# LAN.net
KiCad netlist of a schematic drawn in Altium Designer
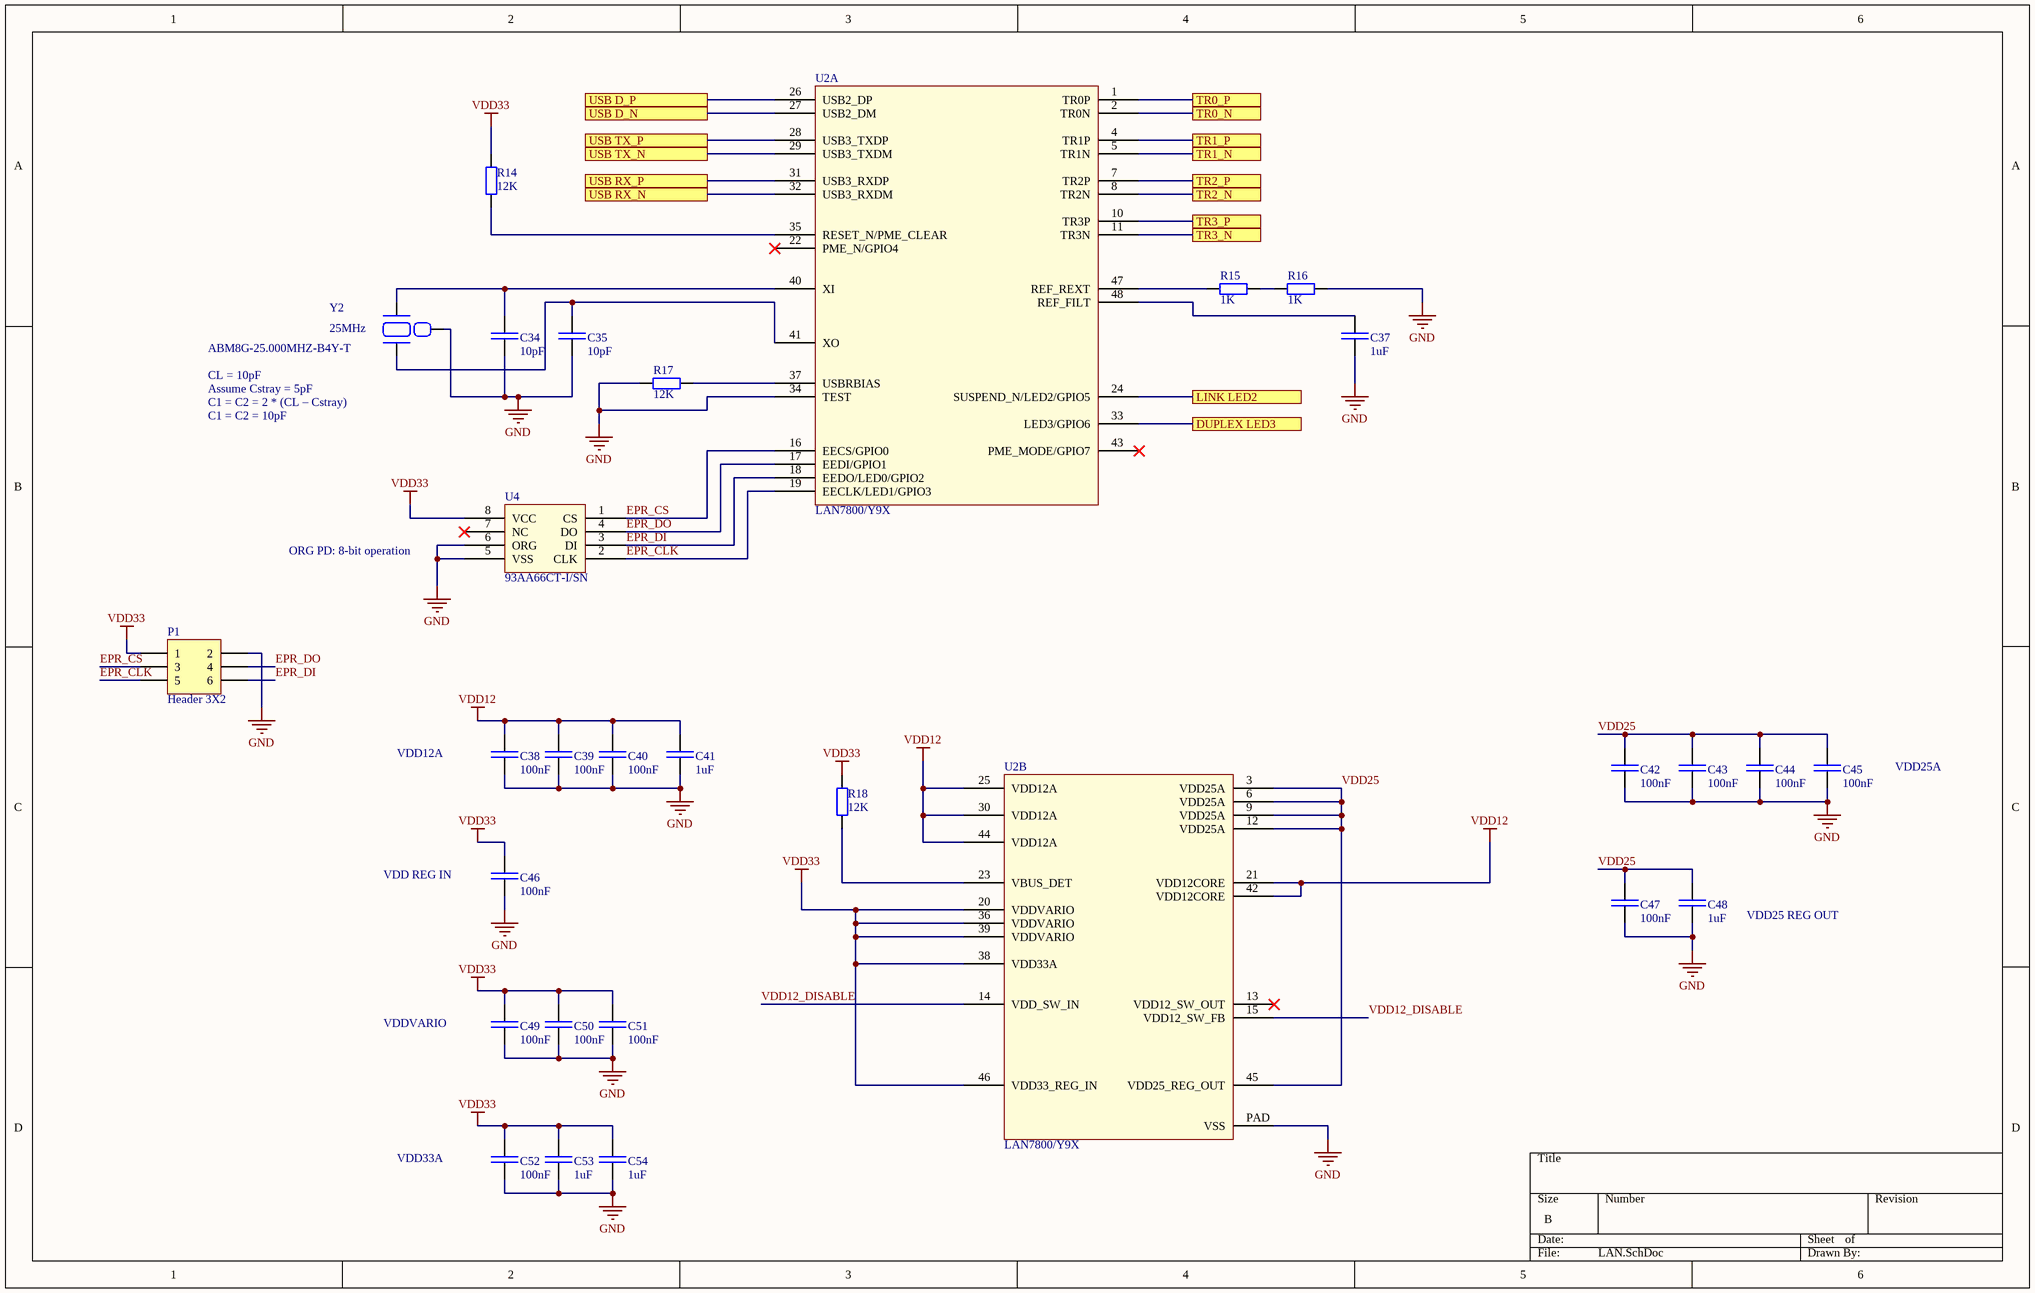
[diagram p0: LAN.SchDoc]

(export (version "E")
  (design (tool "Eeschema 10.0.6"))
  (components
    (comp (ref "C34")
      (value "10pF")
      (footprint "CAP_SM0603_YAGEOCC2_N")
      (description "CAP 10pF SM0603 NPO 50V YAGEO CC2")
      (fields
        (field (name "MANUFACTURER") "Yageo")
        (field (name "MANUFACTURER PART NUMBER") "CC0603JRNPO9BN100")
      )
      (libsource (lib "Yageo") (part "CC0603JRNPO9BN100"))
    )
    (comp (ref "C35")
      (value "10pF")
      (footprint "CAP_SM0603_YAGEOCC2_N")
      (description "CAP 10pF SM0603 NPO 50V YAGEO CC2")
      (fields
        (field (name "MANUFACTURER") "Yageo")
        (field (name "MANUFACTURER PART NUMBER") "CC0603JRNPO9BN100")
      )
      (libsource (lib "Yageo") (part "CC0603JRNPO9BN100"))
    )
    (comp (ref "C37")
      (value "1uF")
      (footprint "CAP_SM0805_YAGEOCC2_N")
      (description "CAP 1uF SM0805 X7R 25V YAGEO CC2")
      (fields
        (field (name "MANUFACTURER") "Yageo")
        (field (name "MANUFACTURER PART NUMBER") "CC0805KKX7R8BB105")
      )
      (libsource (lib "Yageo") (part "CC0805KKX7R8BB105"))
    )
    (comp (ref "C38")
      (value "100nF")
      (footprint "CAP_SM0603_YAGEOCC2_N")
      (description "CAP 100nF SM0603 X7R 50V YAGEO CC2")
      (fields
        (field (name "MANUFACTURER") "Yageo")
        (field (name "MANUFACTURER PART NUMBER") "CC0603KRX7R9BB104")
      )
      (libsource (lib "Yageo") (part "CC0603KRX7R9BB104"))
    )
    (comp (ref "C39")
      (value "100nF")
      (footprint "CAP_SM0603_YAGEOCC2_N")
      (description "CAP 100nF SM0603 X7R 50V YAGEO CC2")
      (fields
        (field (name "MANUFACTURER") "Yageo")
        (field (name "MANUFACTURER PART NUMBER") "CC0603KRX7R9BB104")
      )
      (libsource (lib "Yageo") (part "CC0603KRX7R9BB104"))
    )
    (comp (ref "C40")
      (value "100nF")
      (footprint "CAP_SM0603_YAGEOCC2_N")
      (description "CAP 100nF SM0603 X7R 50V YAGEO CC2")
      (fields
        (field (name "MANUFACTURER") "Yageo")
        (field (name "MANUFACTURER PART NUMBER") "CC0603KRX7R9BB104")
      )
      (libsource (lib "Yageo") (part "CC0603KRX7R9BB104"))
    )
    (comp (ref "C41")
      (value "1uF")
      (footprint "CAP_SM0805_YAGEOCC2_N")
      (description "CAP 1uF SM0805 X7R 25V YAGEO CC2")
      (fields
        (field (name "MANUFACTURER") "Yageo")
        (field (name "MANUFACTURER PART NUMBER") "CC0805KKX7R8BB105")
      )
      (libsource (lib "Yageo") (part "CC0805KKX7R8BB105"))
    )
    (comp (ref "C42")
      (value "100nF")
      (footprint "CAP_SM0603_YAGEOCC2_N")
      (description "CAP 100nF SM0603 X7R 50V YAGEO CC2")
      (fields
        (field (name "MANUFACTURER") "Yageo")
        (field (name "MANUFACTURER PART NUMBER") "CC0603KRX7R9BB104")
      )
      (libsource (lib "Yageo") (part "CC0603KRX7R9BB104"))
    )
    (comp (ref "C43")
      (value "100nF")
      (footprint "CAP_SM0603_YAGEOCC2_N")
      (description "CAP 100nF SM0603 X7R 50V YAGEO CC2")
      (fields
        (field (name "MANUFACTURER") "Yageo")
        (field (name "MANUFACTURER PART NUMBER") "CC0603KRX7R9BB104")
      )
      (libsource (lib "Yageo") (part "CC0603KRX7R9BB104"))
    )
    (comp (ref "C44")
      (value "100nF")
      (footprint "CAP_SM0603_YAGEOCC2_N")
      (description "CAP 100nF SM0603 X7R 50V YAGEO CC2")
      (fields
        (field (name "MANUFACTURER") "Yageo")
        (field (name "MANUFACTURER PART NUMBER") "CC0603KRX7R9BB104")
      )
      (libsource (lib "Yageo") (part "CC0603KRX7R9BB104"))
    )
    (comp (ref "C45")
      (value "100nF")
      (footprint "CAP_SM0603_YAGEOCC2_N")
      (description "CAP 100nF SM0603 X7R 50V YAGEO CC2")
      (fields
        (field (name "MANUFACTURER") "Yageo")
        (field (name "MANUFACTURER PART NUMBER") "CC0603KRX7R9BB104")
      )
      (libsource (lib "Yageo") (part "CC0603KRX7R9BB104"))
    )
    (comp (ref "C46")
      (value "100nF")
      (footprint "CAP_SM0603_YAGEOCC2_N")
      (description "CAP 100nF SM0603 X7R 50V YAGEO CC2")
      (fields
        (field (name "MANUFACTURER") "Yageo")
        (field (name "MANUFACTURER PART NUMBER") "CC0603KRX7R9BB104")
      )
      (libsource (lib "Yageo") (part "CC0603KRX7R9BB104"))
    )
    (comp (ref "C47")
      (value "100nF")
      (footprint "CAP_SM0603_YAGEOCC2_N")
      (description "CAP 100nF SM0603 X7R 50V YAGEO CC2")
      (fields
        (field (name "MANUFACTURER") "Yageo")
        (field (name "MANUFACTURER PART NUMBER") "CC0603KRX7R9BB104")
      )
      (libsource (lib "Yageo") (part "CC0603KRX7R9BB104"))
    )
    (comp (ref "C48")
      (value "1uF")
      (footprint "CAP_SM0805_YAGEOCC2_N")
      (description "CAP 1uF SM0805 X7R 25V YAGEO CC2")
      (fields
        (field (name "MANUFACTURER") "Yageo")
        (field (name "MANUFACTURER PART NUMBER") "CC0805KKX7R8BB105")
      )
      (libsource (lib "Yageo") (part "CC0805KKX7R8BB105"))
    )
    (comp (ref "C49")
      (value "100nF")
      (footprint "CAP_SM0603_YAGEOCC2_N")
      (description "CAP 100nF SM0603 X7R 50V YAGEO CC2")
      (fields
        (field (name "MANUFACTURER") "Yageo")
        (field (name "MANUFACTURER PART NUMBER") "CC0603KRX7R9BB104")
      )
      (libsource (lib "Yageo") (part "CC0603KRX7R9BB104"))
    )
    (comp (ref "C50")
      (value "100nF")
      (footprint "CAP_SM0603_YAGEOCC2_N")
      (description "CAP 100nF SM0603 X7R 50V YAGEO CC2")
      (fields
        (field (name "MANUFACTURER") "Yageo")
        (field (name "MANUFACTURER PART NUMBER") "CC0603KRX7R9BB104")
      )
      (libsource (lib "Yageo") (part "CC0603KRX7R9BB104"))
    )
    (comp (ref "C51")
      (value "100nF")
      (footprint "CAP_SM0603_YAGEOCC2_N")
      (description "CAP 100nF SM0603 X7R 50V YAGEO CC2")
      (fields
        (field (name "MANUFACTURER") "Yageo")
        (field (name "MANUFACTURER PART NUMBER") "CC0603KRX7R9BB104")
      )
      (libsource (lib "Yageo") (part "CC0603KRX7R9BB104"))
    )
    (comp (ref "C52")
      (value "100nF")
      (footprint "CAP_SM0603_YAGEOCC2_N")
      (description "CAP 100nF SM0603 X7R 50V YAGEO CC2")
      (fields
        (field (name "MANUFACTURER") "Yageo")
        (field (name "MANUFACTURER PART NUMBER") "CC0603KRX7R9BB104")
      )
      (libsource (lib "Yageo") (part "CC0603KRX7R9BB104"))
    )
    (comp (ref "C53")
      (value "1uF")
      (footprint "CAP_SM0805_YAGEOCC2_N")
      (description "CAP 1uF SM0805 X7R 25V YAGEO CC2")
      (fields
        (field (name "MANUFACTURER") "Yageo")
        (field (name "MANUFACTURER PART NUMBER") "CC0805KKX7R8BB105")
      )
      (libsource (lib "Yageo") (part "CC0805KKX7R8BB105"))
    )
    (comp (ref "C54")
      (value "1uF")
      (footprint "CAP_SM0805_YAGEOCC2_N")
      (description "CAP 1uF SM0805 X7R 25V YAGEO CC2")
      (fields
        (field (name "MANUFACTURER") "Yageo")
        (field (name "MANUFACTURER PART NUMBER") "CC0805KKX7R8BB105")
      )
      (libsource (lib "Yageo") (part "CC0805KKX7R8BB105"))
    )
    (comp (ref "P1")
      (value "Header 3X2")
      (footprint "HDR2X3")
      (description "Header, 3-Pin, Dual row")
      (fields (field (name "PUBLISHER") "Altium Limited"))
      (libsource (lib "Miscellaneous Connectors") (part "Header 3X2"))
    )
    (comp (ref "R14")
      (value "12K")
      (footprint "RES_SM0603_YAGEORC_N")
      (description "RES 12K SM0603 YAGEO RC_L")
      (fields
        (field (name "MANUFACTURER") "Yageo")
        (field (name "MANUFACTURER PART NUMBER") "RC0603FR-0712KL")
      )
      (libsource (lib "Yageo") (part "RC0603FR-0712KL"))
    )
    (comp (ref "R15")
      (value "1K")
      (footprint "RES_SM0603_YAGEORC_N")
      (description "RES 1K SM0603 YAGEO RC_L")
      (fields
        (field (name "MANUFACTURER") "Yageo")
        (field (name "MANUFACTURER PART NUMBER") "RC0603FR-071KL")
      )
      (libsource (lib "Yageo") (part "RC0603FR-071KL"))
    )
    (comp (ref "R16")
      (value "1K")
      (footprint "RES_SM0603_YAGEORC_N")
      (description "RES 1K SM0603 YAGEO RC_L")
      (fields
        (field (name "MANUFACTURER") "Yageo")
        (field (name "MANUFACTURER PART NUMBER") "RC0603FR-071KL")
      )
      (libsource (lib "Yageo") (part "RC0603FR-071KL"))
    )
    (comp (ref "R17")
      (value "12K")
      (footprint "RES_SM0603_YAGEORC_N")
      (description "RES 12K SM0603 YAGEO RC_L")
      (fields
        (field (name "MANUFACTURER") "Yageo")
        (field (name "MANUFACTURER PART NUMBER") "RC0603FR-0712KL")
      )
      (libsource (lib "") (part "RC0603FR-0712KL_1"))
    )
    (comp (ref "R18")
      (value "12K")
      (footprint "RES_SM0603_YAGEORC_N")
      (description "RES 12K SM0603 YAGEO RC_L")
      (fields
        (field (name "MANUFACTURER") "Yageo")
        (field (name "MANUFACTURER PART NUMBER") "RC0603FR-0712KL")
      )
      (libsource (lib "Yageo") (part "RC0603FR-0712KL"))
    )
    (comp (ref "U2")
      (value "LAN7800/Y9X")
      (footprint "QFN50P700X700X100_HS-49N - LAN7800/Y9X")
      (description "IC ETHERNET CTLR USB 48SQFN 7x7")
      (libsource (lib "KBuchka-IntLib") (part "LAN7800/Y9X"))
    )
    (comp (ref "U4")
      (value "93AA66CT-I/SN")
      (footprint "SOIC127P600X175-8N - 93AA66CT-I/SN")
      (description "IC EEPROM 4KBIT MICROWIRE 8SOIC")
      (libsource (lib "KBuchka-IntLib") (part "93AA66CT-I/SN"))
    )
    (comp (ref "Y2")
      (value "ABM8G-25.000MHZ-B4Y-T")
      (footprint "ABM8G-25.000MHZ-B4Y-T")
      (description "CRYSTAL 25.0000MHZ 10PF SMD")
      (libsource (lib "KBuchka-IntLib") (part "ABM8G-25.000MHZ-B4Y-T"))
    )
  )
  (nets
    (net (code "1") (name "/DUPLEX LED3") (class "Default")
      (node (ref "U2") (pin "33") (pinfunction "LED3/GPIO6_33") (pintype "passive"))
    )
    (net (code "2") (name "/EPR_CLK") (class "Default")
      (node (ref "P1") (pin "5") (pinfunction "5_5") (pintype "passive"))
      (node (ref "U2") (pin "19") (pinfunction "EECLK/LED1/GPIO3_19") (pintype "passive"))
      (node (ref "U4") (pin "2") (pinfunction "CLK_2") (pintype "passive"))
    )
    (net (code "3") (name "/EPR_CS") (class "Default")
      (node (ref "P1") (pin "3") (pinfunction "3_3") (pintype "passive"))
      (node (ref "U2") (pin "16") (pinfunction "EECS/GPIO0_16") (pintype "passive"))
      (node (ref "U4") (pin "1") (pinfunction "CS_1") (pintype "passive"))
    )
    (net (code "4") (name "/EPR_DI") (class "Default")
      (node (ref "P1") (pin "6") (pinfunction "6_6") (pintype "passive"))
      (node (ref "U2") (pin "18") (pinfunction "EEDO/LED0/GPIO2_18") (pintype "passive"))
      (node (ref "U4") (pin "3") (pinfunction "DI_3") (pintype "passive"))
    )
    (net (code "5") (name "/EPR_DO") (class "Default")
      (node (ref "P1") (pin "4") (pinfunction "4_4") (pintype "passive"))
      (node (ref "U2") (pin "17") (pinfunction "EEDI/GPIO1_17") (pintype "passive"))
      (node (ref "U4") (pin "4") (pinfunction "DO_4") (pintype "passive"))
    )
    (net (code "6") (name "/LINK LED2") (class "Default")
      (node (ref "U2") (pin "24") (pinfunction "SUSPEND_N/LED2/GPIO5_24") (pintype "passive"))
    )
    (net (code "7") (name "/TR0_N") (class "Default")
      (node (ref "U2") (pin "2") (pinfunction "TR0N_2") (pintype "passive"))
    )
    (net (code "8") (name "/TR0_P") (class "Default")
      (node (ref "U2") (pin "1") (pinfunction "TR0P_1") (pintype "passive"))
    )
    (net (code "9") (name "/TR1_N") (class "Default")
      (node (ref "U2") (pin "5") (pinfunction "TR1N_5") (pintype "passive"))
    )
    (net (code "10") (name "/TR1_P") (class "Default")
      (node (ref "U2") (pin "4") (pinfunction "TR1P_4") (pintype "passive"))
    )
    (net (code "11") (name "/TR2_N") (class "Default")
      (node (ref "U2") (pin "8") (pinfunction "TR2N_8") (pintype "passive"))
    )
    (net (code "12") (name "/TR2_P") (class "Default")
      (node (ref "U2") (pin "7") (pinfunction "TR2P_7") (pintype "passive"))
    )
    (net (code "13") (name "/TR3_N") (class "Default")
      (node (ref "U2") (pin "11") (pinfunction "TR3N_11") (pintype "passive"))
    )
    (net (code "14") (name "/TR3_P") (class "Default")
      (node (ref "U2") (pin "10") (pinfunction "TR3P_10") (pintype "passive"))
    )
    (net (code "15") (name "/USB D_N") (class "Default")
      (node (ref "U2") (pin "27") (pinfunction "USB2_DM_27") (pintype "passive"))
    )
    (net (code "16") (name "/USB D_P") (class "Default")
      (node (ref "U2") (pin "26") (pinfunction "USB2_DP_26") (pintype "passive"))
    )
    (net (code "17") (name "/USB RX_N") (class "Default")
      (node (ref "U2") (pin "32") (pinfunction "USB3_RXDM_32") (pintype "passive"))
    )
    (net (code "18") (name "/USB RX_P") (class "Default")
      (node (ref "U2") (pin "31") (pinfunction "USB3_RXDP_31") (pintype "passive"))
    )
    (net (code "19") (name "/USB TX_N") (class "Default")
      (node (ref "U2") (pin "29") (pinfunction "USB3_TXDM_29") (pintype "passive"))
    )
    (net (code "20") (name "/USB TX_P") (class "Default")
      (node (ref "U2") (pin "28") (pinfunction "USB3_TXDP_28") (pintype "passive"))
    )
    (net (code "21") (name "/VDD12_DISABLE") (class "Default")
      (node (ref "U2") (pin "14") (pinfunction "VDD_SW_IN_14") (pintype "passive"))
      (node (ref "U2") (pin "15") (pinfunction "VDD12_SW_FB_15") (pintype "passive"))
    )
    (net (code "22") (name "/VDD25") (class "Default")
      (node (ref "C42") (pin "1") (pintype "passive"))
      (node (ref "C43") (pin "1") (pintype "passive"))
      (node (ref "C44") (pin "1") (pintype "passive"))
      (node (ref "C45") (pin "1") (pintype "passive"))
      (node (ref "C47") (pin "1") (pintype "passive"))
      (node (ref "C48") (pin "1") (pintype "passive"))
      (node (ref "U2") (pin "12") (pinfunction "VDD25A_12") (pintype "passive"))
      (node (ref "U2") (pin "3") (pinfunction "VDD25A_3") (pintype "passive"))
      (node (ref "U2") (pin "45") (pinfunction "VDD25_REG_OUT_45") (pintype "passive"))
      (node (ref "U2") (pin "6") (pinfunction "VDD25A_6") (pintype "passive"))
      (node (ref "U2") (pin "9") (pinfunction "VDD25A_9") (pintype "passive"))
    )
    (net (code "23") (name "GND") (class "Default")
      (node (ref "C34") (pin "2") (pintype "passive"))
      (node (ref "C35") (pin "2") (pintype "passive"))
      (node (ref "C37") (pin "2") (pintype "passive"))
      (node (ref "C38") (pin "2") (pintype "passive"))
      (node (ref "C39") (pin "2") (pintype "passive"))
      (node (ref "C40") (pin "2") (pintype "passive"))
      (node (ref "C41") (pin "2") (pintype "passive"))
      (node (ref "C42") (pin "2") (pintype "passive"))
      (node (ref "C43") (pin "2") (pintype "passive"))
      (node (ref "C44") (pin "2") (pintype "passive"))
      (node (ref "C45") (pin "2") (pintype "passive"))
      (node (ref "C46") (pin "2") (pintype "passive"))
      (node (ref "C47") (pin "2") (pintype "passive"))
      (node (ref "C48") (pin "2") (pintype "passive"))
      (node (ref "C49") (pin "2") (pintype "passive"))
      (node (ref "C50") (pin "2") (pintype "passive"))
      (node (ref "C51") (pin "2") (pintype "passive"))
      (node (ref "C52") (pin "2") (pintype "passive"))
      (node (ref "C53") (pin "2") (pintype "passive"))
      (node (ref "C54") (pin "2") (pintype "passive"))
      (node (ref "P1") (pin "2") (pinfunction "2_2") (pintype "passive"))
      (node (ref "R16") (pin "2") (pintype "passive"))
      (node (ref "R17") (pin "1") (pintype "passive"))
      (node (ref "U2") (pin "34") (pinfunction "TEST_34") (pintype "passive"))
      (node (ref "U2") (pin "PAD") (pinfunction "VSS_PAD") (pintype "passive"))
      (node (ref "U4") (pin "5") (pinfunction "VSS_5") (pintype "passive"))
      (node (ref "U4") (pin "6") (pinfunction "ORG_6") (pintype "passive"))
      (node (ref "Y2") (pin "GND") (pinfunction "4_GND") (pintype "passive"))
    )
    (net (code "24") (name "Net-(R15-Pad2)") (class "Default")
      (node (ref "R15") (pin "2") (pintype "passive"))
      (node (ref "R16") (pin "1") (pintype "passive"))
    )
    (net (code "25") (name "Net-(U2A-REF_FILT)") (class "Default")
      (node (ref "C37") (pin "1") (pintype "passive"))
      (node (ref "U2") (pin "48") (pinfunction "REF_FILT_48") (pintype "passive"))
    )
    (net (code "26") (name "Net-(U2A-REF_REXT)") (class "Default")
      (node (ref "R15") (pin "1") (pintype "passive"))
      (node (ref "U2") (pin "47") (pinfunction "REF_REXT_47") (pintype "passive"))
    )
    (net (code "27") (name "Net-(U2A-RESET_N{slash}PME_CLEAR)") (class "Default")
      (node (ref "R14") (pin "1") (pintype "passive"))
      (node (ref "U2") (pin "35") (pinfunction "RESET_N/PME_CLEAR_35") (pintype "passive"))
    )
    (net (code "28") (name "Net-(U2A-USBRBIAS)") (class "Default")
      (node (ref "R17") (pin "2") (pintype "passive"))
      (node (ref "U2") (pin "37") (pinfunction "USBRBIAS_37") (pintype "passive"))
    )
    (net (code "29") (name "Net-(U2A-XI)") (class "Default")
      (node (ref "C34") (pin "1") (pintype "passive"))
      (node (ref "U2") (pin "40") (pinfunction "XI_40") (pintype "passive"))
      (node (ref "Y2") (pin "1") (pinfunction "1_1") (pintype "passive"))
    )
    (net (code "30") (name "Net-(U2A-XO)") (class "Default")
      (node (ref "C35") (pin "1") (pintype "passive"))
      (node (ref "U2") (pin "41") (pinfunction "XO_41") (pintype "passive"))
      (node (ref "Y2") (pin "3") (pinfunction "3_3") (pintype "passive"))
    )
    (net (code "31") (name "Net-(U2B-VBUS_DET)") (class "Default")
      (node (ref "R18") (pin "1") (pintype "passive"))
      (node (ref "U2") (pin "23") (pinfunction "VBUS_DET_23") (pintype "passive"))
    )
    (net (code "32") (name "VDD12") (class "Default")
      (node (ref "C38") (pin "1") (pintype "passive"))
      (node (ref "C39") (pin "1") (pintype "passive"))
      (node (ref "C40") (pin "1") (pintype "passive"))
      (node (ref "C41") (pin "1") (pintype "passive"))
      (node (ref "U2") (pin "21") (pinfunction "VDD12CORE_21") (pintype "passive"))
      (node (ref "U2") (pin "25") (pinfunction "VDD12A_25") (pintype "passive"))
      (node (ref "U2") (pin "30") (pinfunction "VDD12A_30") (pintype "passive"))
      (node (ref "U2") (pin "42") (pinfunction "VDD12CORE_42") (pintype "passive"))
      (node (ref "U2") (pin "44") (pinfunction "VDD12A_44") (pintype "passive"))
    )
    (net (code "33") (name "VDD33") (class "Default")
      (node (ref "C46") (pin "1") (pintype "passive"))
      (node (ref "C49") (pin "1") (pintype "passive"))
      (node (ref "C50") (pin "1") (pintype "passive"))
      (node (ref "C51") (pin "1") (pintype "passive"))
      (node (ref "C52") (pin "1") (pintype "passive"))
      (node (ref "C53") (pin "1") (pintype "passive"))
      (node (ref "C54") (pin "1") (pintype "passive"))
      (node (ref "P1") (pin "1") (pinfunction "1_1") (pintype "passive"))
      (node (ref "R14") (pin "2") (pintype "passive"))
      (node (ref "R18") (pin "2") (pintype "passive"))
      (node (ref "U2") (pin "20") (pinfunction "VDDVARIO_20") (pintype "passive"))
      (node (ref "U2") (pin "36") (pinfunction "VDDVARIO_36") (pintype "passive"))
      (node (ref "U2") (pin "38") (pinfunction "VDD33A_38") (pintype "passive"))
      (node (ref "U2") (pin "39") (pinfunction "VDDVARIO_39") (pintype "passive"))
      (node (ref "U2") (pin "46") (pinfunction "VDD33_REG_IN_46") (pintype "passive"))
      (node (ref "U4") (pin "8") (pinfunction "VCC_8") (pintype "passive"))
    )
    (net (code "34") (name "unconnected-(U2A-PME_MODE{slash}GPIO7-Pad43)") (class "Default")
      (node (ref "U2") (pin "43") (pinfunction "PME_MODE/GPIO7_43") (pintype "passive+no_connect"))
    )
    (net (code "35") (name "unconnected-(U2A-PME_N{slash}GPIO4-Pad22)") (class "Default")
      (node (ref "U2") (pin "22") (pinfunction "PME_N/GPIO4_22") (pintype "passive+no_connect"))
    )
    (net (code "36") (name "unconnected-(U2B-VDD12_SW_OUT-Pad13)") (class "Default")
      (node (ref "U2") (pin "13") (pinfunction "VDD12_SW_OUT_13") (pintype "passive+no_connect"))
    )
    (net (code "37") (name "unconnected-(U4-NC-Pad7)") (class "Default")
      (node (ref "U4") (pin "7") (pinfunction "NC_7") (pintype "passive+no_connect"))
    )
  )
)
